# VOLTAGE_MONITOR.net
KiCad netlist of a schematic drawn in Altium Designer
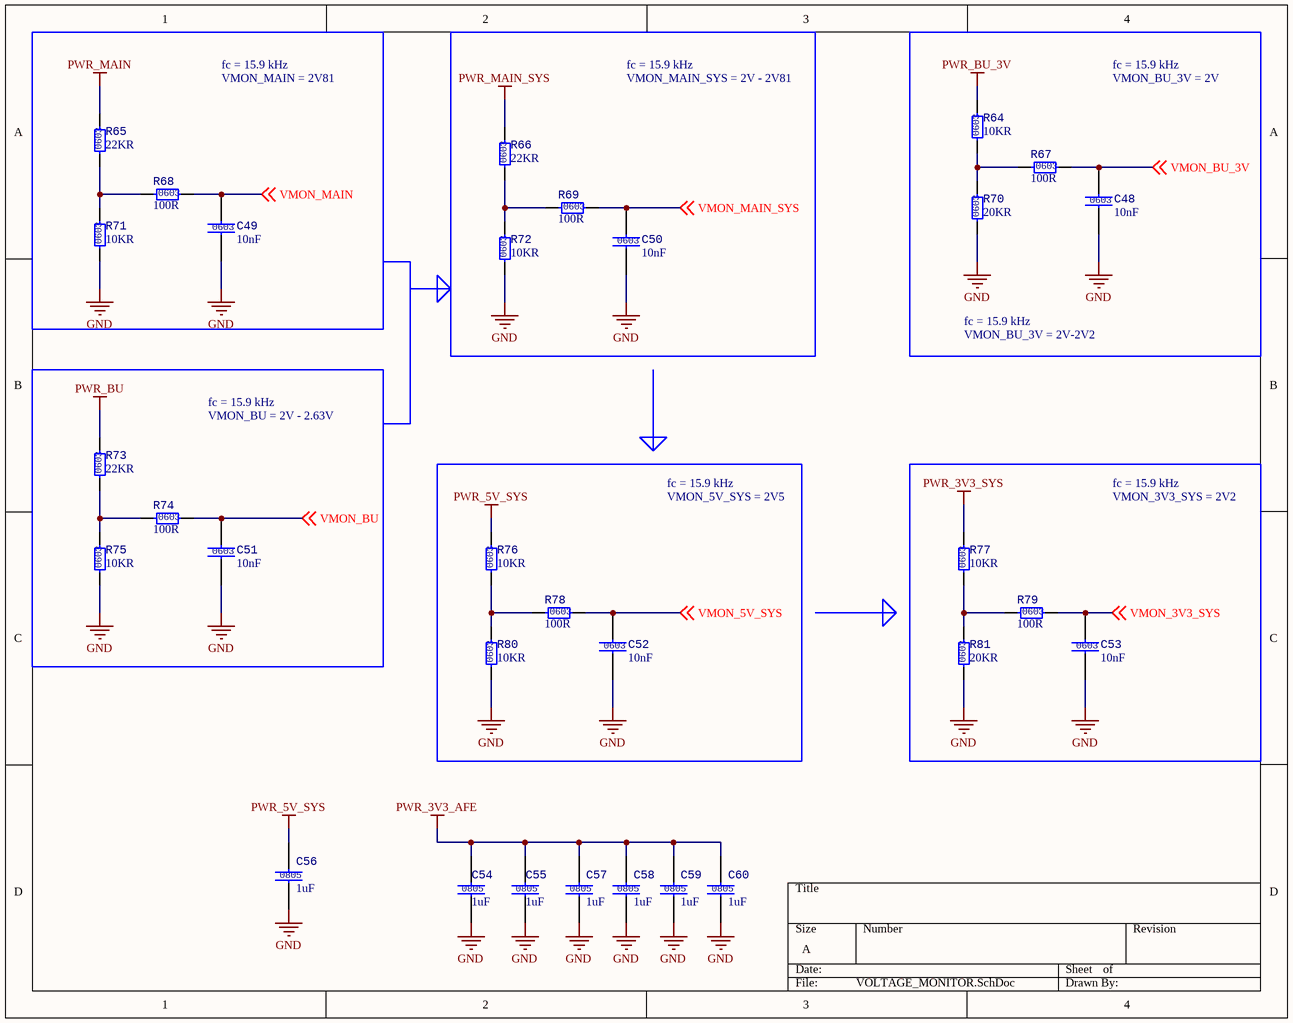
[diagram p0: VOLTAGE_MONITOR.SchDoc]

(export (version "E")
  (design (tool "Eeschema 10.0.6"))
  (components
    (comp (ref "C48")
      (value "10nF")
      (footprint "CAPCER 0805 SMD")
      (description "CAPACITOR SMD 0.01uF 50V 10% 0603")
      (fields
        (field (name "SIZE") "0603")
        (field (name "TOLERANCE") "10%")
        (field (name "Comment") "Tụ Gốm 0603 10nF 50V")
      )
      (libsource (lib "Database_Libs1") (part "CAPACITOR"))
    )
    (comp (ref "C49")
      (value "10nF")
      (footprint "CAPCER 0805 SMD")
      (description "CAPACITOR SMD 0.01uF 50V 10% 0603")
      (fields
        (field (name "SIZE") "0603")
        (field (name "TOLERANCE") "10%")
        (field (name "Comment") "Tụ Gốm 0603 10nF 50V")
      )
      (libsource (lib "Database_Libs1") (part "CAPACITOR"))
    )
    (comp (ref "C50")
      (value "10nF")
      (footprint "CAPCER 0805 SMD")
      (description "CAPACITOR SMD 0.01uF 50V 10% 0603")
      (fields
        (field (name "SIZE") "0603")
        (field (name "TOLERANCE") "10%")
        (field (name "Comment") "Tụ Gốm 0603 10nF 50V")
      )
      (libsource (lib "Database_Libs1") (part "CAPACITOR"))
    )
    (comp (ref "C51")
      (value "10nF")
      (footprint "CAPCER 0805 SMD")
      (description "CAPACITOR SMD 0.01uF 50V 10% 0603")
      (fields
        (field (name "SIZE") "0603")
        (field (name "TOLERANCE") "10%")
        (field (name "Comment") "Tụ Gốm 0603 10nF 50V")
      )
      (libsource (lib "Database_Libs1") (part "CAPACITOR"))
    )
    (comp (ref "C52")
      (value "10nF")
      (footprint "CAPCER 0805 SMD")
      (description "CAPACITOR SMD 0.01uF 50V 10% 0603")
      (fields
        (field (name "SIZE") "0603")
        (field (name "TOLERANCE") "10%")
        (field (name "Comment") "Tụ Gốm 0603 10nF 50V")
      )
      (libsource (lib "Database_Libs1") (part "CAPACITOR"))
    )
    (comp (ref "C53")
      (value "10nF")
      (footprint "CAPCER 0805 SMD")
      (description "CAPACITOR SMD 0.01uF 50V 10% 0603")
      (fields
        (field (name "SIZE") "0603")
        (field (name "TOLERANCE") "10%")
        (field (name "Comment") "Tụ Gốm 0603 10nF 50V")
      )
      (libsource (lib "Database_Libs1") (part "CAPACITOR"))
    )
    (comp (ref "C54")
      (value "1uF")
      (footprint "CAPCER 0805 SMD")
      (description "CAPACITOR SMD 1uF 16V 10% 0805")
      (fields (field (name "SIZE") "0805") (field (name "TOLERANCE") "10%"))
      (libsource (lib "Database_Libs1") (part "CAPACITOR"))
    )
    (comp (ref "C55")
      (value "1uF")
      (footprint "CAPCER 0805 SMD")
      (description "CAPACITOR SMD 1uF 16V 10% 0805")
      (fields (field (name "SIZE") "0805") (field (name "TOLERANCE") "10%"))
      (libsource (lib "Database_Libs1") (part "CAPACITOR"))
    )
    (comp (ref "C56")
      (value "1uF")
      (footprint "CAPCER 0805 SMD")
      (description "CAPACITOR SMD 1uF 16V 10% 0805")
      (fields (field (name "SIZE") "0805") (field (name "TOLERANCE") "10%"))
      (libsource (lib "Database_Libs1") (part "CAPACITOR"))
    )
    (comp (ref "C57")
      (value "1uF")
      (footprint "CAPCER 0805 SMD")
      (description "CAPACITOR SMD 1uF 16V 10% 0805")
      (fields (field (name "SIZE") "0805") (field (name "TOLERANCE") "10%"))
      (libsource (lib "Database_Libs1") (part "CAPACITOR"))
    )
    (comp (ref "C58")
      (value "1uF")
      (footprint "CAPCER 0603 SMD")
      (description "CAPACITOR SMD 1uF 16V 10% 0805")
      (fields (field (name "SIZE") "0805") (field (name "TOLERANCE") "10%") (field (name "Comment") "10uF"))
      (libsource (lib "Database_Libs1") (part "CAPACITOR"))
    )
    (comp (ref "C59")
      (value "1uF")
      (footprint "CAPCER 0805 SMD")
      (description "CAPACITOR SMD 1uF 16V 10% 0805")
      (fields (field (name "SIZE") "0805") (field (name "TOLERANCE") "10%"))
      (libsource (lib "Database_Libs1") (part "CAPACITOR"))
    )
    (comp (ref "C60")
      (value "1uF")
      (footprint "CAPCER 0603 SMD")
      (description "CAPACITOR SMD 1uF 16V 10% 0805")
      (fields (field (name "SIZE") "0805") (field (name "TOLERANCE") "10%") (field (name "Comment") "10uF"))
      (libsource (lib "Database_Libs1") (part "CAPACITOR"))
    )
    (comp (ref "R64")
      (value "10KR")
      (footprint "RESC 0603(1608) SMD")
      (description "RESISTOR SMD 10KR OHM 1% 100mW 0603")
      (fields (field (name "SIZE") "0603") (field (name "TOLERANCE") "1%"))
      (libsource (lib "Database_Libs1") (part "RESISTOR"))
    )
    (comp (ref "R65")
      (value "22KR")
      (footprint "RESC 0603(1608) SMD")
      (description "Điện Trở 22 KOhm 0603 1%")
      (fields (field (name "SIZE") "0603"))
      (libsource (lib "") (part "RESISTOR_1"))
    )
    (comp (ref "R66")
      (value "22KR")
      (footprint "RESC 0603(1608) SMD")
      (description "Điện Trở 22 KOhm 0603 1%")
      (fields (field (name "SIZE") "0603"))
      (libsource (lib "") (part "RESISTOR_1"))
    )
    (comp (ref "R67")
      (value "100R")
      (footprint "RESC 0603(1608) SMD")
      (description "Điện Trở 100 Ohm 0603 1%")
      (fields (field (name "SIZE") "0603"))
      (libsource (lib "Database_Libs2") (part "RESISTOR"))
    )
    (comp (ref "R68")
      (value "100R")
      (footprint "RESC 0603(1608) SMD")
      (description "Điện Trở 100 Ohm 0603 1%")
      (fields (field (name "SIZE") "0603"))
      (libsource (lib "Database_Libs2") (part "RESISTOR"))
    )
    (comp (ref "R69")
      (value "100R")
      (footprint "RESC 0603(1608) SMD")
      (description "Điện Trở 100 Ohm 0603 1%")
      (fields (field (name "SIZE") "0603"))
      (libsource (lib "Database_Libs2") (part "RESISTOR"))
    )
    (comp (ref "R70")
      (value "20KR")
      (footprint "RESC 0603(1608) SMD")
      (description "Điện Trở 20 KOhm 0603 1%")
      (fields (field (name "SIZE") "0603"))
      (libsource (lib "") (part "RESISTOR_1"))
    )
    (comp (ref "R71")
      (value "10KR")
      (footprint "RESC 0603(1608) SMD")
      (description "RESISTOR SMD 10KR OHM 1% 100mW 0603")
      (fields (field (name "SIZE") "0603") (field (name "TOLERANCE") "1%"))
      (libsource (lib "Database_Libs1") (part "RESISTOR"))
    )
    (comp (ref "R72")
      (value "10KR")
      (footprint "RESC 0603(1608) SMD")
      (description "RESISTOR SMD 10KR OHM 1% 100mW 0603")
      (fields (field (name "SIZE") "0603") (field (name "TOLERANCE") "1%"))
      (libsource (lib "Database_Libs1") (part "RESISTOR"))
    )
    (comp (ref "R73")
      (value "22KR")
      (footprint "RESC 0603(1608) SMD")
      (description "Điện Trở 22 KOhm 0603 1%")
      (fields (field (name "SIZE") "0603"))
      (libsource (lib "") (part "RESISTOR_1"))
    )
    (comp (ref "R74")
      (value "100R")
      (footprint "RESC 0603(1608) SMD")
      (description "Điện Trở 100 Ohm 0603 1%")
      (fields (field (name "SIZE") "0603"))
      (libsource (lib "Database_Libs2") (part "RESISTOR"))
    )
    (comp (ref "R75")
      (value "10KR")
      (footprint "RESC 0603(1608) SMD")
      (description "RESISTOR SMD 10KR OHM 1% 100mW 0603")
      (fields (field (name "SIZE") "0603") (field (name "TOLERANCE") "1%"))
      (libsource (lib "Database_Libs1") (part "RESISTOR"))
    )
    (comp (ref "R76")
      (value "10KR")
      (footprint "RESC 0603(1608) SMD")
      (description "RESISTOR SMD 10KR OHM 1% 100mW 0603")
      (fields (field (name "SIZE") "0603") (field (name "TOLERANCE") "1%"))
      (libsource (lib "Database_Libs1") (part "RESISTOR"))
    )
    (comp (ref "R77")
      (value "10KR")
      (footprint "RESC 0603(1608) SMD")
      (description "RESISTOR SMD 10KR OHM 1% 100mW 0603")
      (fields (field (name "SIZE") "0603") (field (name "TOLERANCE") "1%"))
      (libsource (lib "Database_Libs1") (part "RESISTOR"))
    )
    (comp (ref "R78")
      (value "100R")
      (footprint "RESC 0603(1608) SMD")
      (description "Điện Trở 100 Ohm 0603 1%")
      (fields (field (name "SIZE") "0603"))
      (libsource (lib "Database_Libs2") (part "RESISTOR"))
    )
    (comp (ref "R79")
      (value "100R")
      (footprint "RESC 0603(1608) SMD")
      (description "Điện Trở 100 Ohm 0603 1%")
      (fields (field (name "SIZE") "0603"))
      (libsource (lib "Database_Libs2") (part "RESISTOR"))
    )
    (comp (ref "R80")
      (value "10KR")
      (footprint "RESC 0603(1608) SMD")
      (description "RESISTOR SMD 10KR OHM 1% 100mW 0603")
      (fields (field (name "SIZE") "0603") (field (name "TOLERANCE") "1%"))
      (libsource (lib "Database_Libs1") (part "RESISTOR"))
    )
    (comp (ref "R81")
      (value "20KR")
      (footprint "RESC 0603(1608) SMD")
      (description "Điện Trở 20 KOhm 0603 1%")
      (fields (field (name "SIZE") "0603"))
      (libsource (lib "") (part "RESISTOR_1"))
    )
  )
  (nets
    (net (code "1") (name "GND") (class "Default")
      (node (ref "C48") (pin "2") (pinfunction "2_2") (pintype "passive"))
      (node (ref "C49") (pin "2") (pinfunction "2_2") (pintype "passive"))
      (node (ref "C50") (pin "2") (pinfunction "2_2") (pintype "passive"))
      (node (ref "C51") (pin "2") (pinfunction "2_2") (pintype "passive"))
      (node (ref "C52") (pin "2") (pinfunction "2_2") (pintype "passive"))
      (node (ref "C53") (pin "2") (pinfunction "2_2") (pintype "passive"))
      (node (ref "C54") (pin "2") (pinfunction "2_2") (pintype "passive"))
      (node (ref "C55") (pin "2") (pinfunction "2_2") (pintype "passive"))
      (node (ref "C56") (pin "2") (pinfunction "2_2") (pintype "passive"))
      (node (ref "C57") (pin "2") (pinfunction "2_2") (pintype "passive"))
      (node (ref "C58") (pin "2") (pinfunction "2_2") (pintype "passive"))
      (node (ref "C59") (pin "2") (pinfunction "2_2") (pintype "passive"))
      (node (ref "C60") (pin "2") (pinfunction "2_2") (pintype "passive"))
      (node (ref "R70") (pin "1") (pinfunction "1_1") (pintype "passive"))
      (node (ref "R71") (pin "1") (pinfunction "1_1") (pintype "passive"))
      (node (ref "R72") (pin "1") (pinfunction "1_1") (pintype "passive"))
      (node (ref "R75") (pin "1") (pinfunction "1_1") (pintype "passive"))
      (node (ref "R80") (pin "1") (pinfunction "1_1") (pintype "passive"))
      (node (ref "R81") (pin "1") (pinfunction "1_1") (pintype "passive"))
    )
    (net (code "2") (name "Net-(R64-Pad1)") (class "Default")
      (node (ref "R64") (pin "1") (pinfunction "1_1") (pintype "passive"))
      (node (ref "R67") (pin "1") (pinfunction "1_1") (pintype "passive"))
      (node (ref "R70") (pin "2") (pinfunction "2_2") (pintype "passive"))
    )
    (net (code "3") (name "Net-(R65-Pad1)") (class "Default")
      (node (ref "R65") (pin "1") (pinfunction "1_1") (pintype "passive"))
      (node (ref "R68") (pin "1") (pinfunction "1_1") (pintype "passive"))
      (node (ref "R71") (pin "2") (pinfunction "2_2") (pintype "passive"))
    )
    (net (code "4") (name "Net-(R66-Pad1)") (class "Default")
      (node (ref "R66") (pin "1") (pinfunction "1_1") (pintype "passive"))
      (node (ref "R69") (pin "1") (pinfunction "1_1") (pintype "passive"))
      (node (ref "R72") (pin "2") (pinfunction "2_2") (pintype "passive"))
    )
    (net (code "5") (name "Net-(R73-Pad1)") (class "Default")
      (node (ref "R73") (pin "1") (pinfunction "1_1") (pintype "passive"))
      (node (ref "R74") (pin "1") (pinfunction "1_1") (pintype "passive"))
      (node (ref "R75") (pin "2") (pinfunction "2_2") (pintype "passive"))
    )
    (net (code "6") (name "Net-(R76-Pad1)") (class "Default")
      (node (ref "R76") (pin "1") (pinfunction "1_1") (pintype "passive"))
      (node (ref "R78") (pin "1") (pinfunction "1_1") (pintype "passive"))
      (node (ref "R80") (pin "2") (pinfunction "2_2") (pintype "passive"))
    )
    (net (code "7") (name "Net-(R77-Pad1)") (class "Default")
      (node (ref "R77") (pin "1") (pinfunction "1_1") (pintype "passive"))
      (node (ref "R79") (pin "1") (pinfunction "1_1") (pintype "passive"))
      (node (ref "R81") (pin "2") (pinfunction "2_2") (pintype "passive"))
    )
    (net (code "8") (name "PWR_3V3_AFE") (class "Default")
      (node (ref "C54") (pin "1") (pinfunction "1_1") (pintype "passive"))
      (node (ref "C55") (pin "1") (pinfunction "1_1") (pintype "passive"))
      (node (ref "C57") (pin "1") (pinfunction "1_1") (pintype "passive"))
      (node (ref "C58") (pin "1") (pinfunction "1_1") (pintype "passive"))
      (node (ref "C59") (pin "1") (pinfunction "1_1") (pintype "passive"))
      (node (ref "C60") (pin "1") (pinfunction "1_1") (pintype "passive"))
    )
    (net (code "9") (name "PWR_3V3_SYS") (class "Default")
      (node (ref "R77") (pin "2") (pinfunction "2_2") (pintype "passive"))
    )
    (net (code "10") (name "PWR_5V_SYS") (class "Default")
      (node (ref "C56") (pin "1") (pinfunction "1_1") (pintype "passive"))
      (node (ref "R76") (pin "2") (pinfunction "2_2") (pintype "passive"))
    )
    (net (code "11") (name "PWR_BU") (class "Default")
      (node (ref "R73") (pin "2") (pinfunction "2_2") (pintype "passive"))
    )
    (net (code "12") (name "PWR_BU_3V") (class "Default")
      (node (ref "R64") (pin "2") (pinfunction "2_2") (pintype "passive"))
    )
    (net (code "13") (name "PWR_MAIN") (class "Default")
      (node (ref "R65") (pin "2") (pinfunction "2_2") (pintype "passive"))
    )
    (net (code "14") (name "PWR_MAIN_SYS") (class "Default")
      (node (ref "R66") (pin "2") (pinfunction "2_2") (pintype "passive"))
    )
    (net (code "15") (name "VMON_3V3_SYS") (class "Default")
      (node (ref "C53") (pin "1") (pinfunction "1_1") (pintype "passive"))
      (node (ref "R79") (pin "2") (pinfunction "2_2") (pintype "passive"))
    )
    (net (code "16") (name "VMON_5V_SYS") (class "Default")
      (node (ref "C52") (pin "1") (pinfunction "1_1") (pintype "passive"))
      (node (ref "R78") (pin "2") (pinfunction "2_2") (pintype "passive"))
    )
    (net (code "17") (name "VMON_BU") (class "Default")
      (node (ref "C51") (pin "1") (pinfunction "1_1") (pintype "passive"))
      (node (ref "R74") (pin "2") (pinfunction "2_2") (pintype "passive"))
    )
    (net (code "18") (name "VMON_BU_3V") (class "Default")
      (node (ref "C48") (pin "1") (pinfunction "1_1") (pintype "passive"))
      (node (ref "R67") (pin "2") (pinfunction "2_2") (pintype "passive"))
    )
    (net (code "19") (name "VMON_MAIN") (class "Default")
      (node (ref "C49") (pin "1") (pinfunction "1_1") (pintype "passive"))
      (node (ref "R68") (pin "2") (pinfunction "2_2") (pintype "passive"))
    )
    (net (code "20") (name "VMON_MAIN_SYS") (class "Default")
      (node (ref "C50") (pin "1") (pinfunction "1_1") (pintype "passive"))
      (node (ref "R69") (pin "2") (pinfunction "2_2") (pintype "passive"))
    )
  )
)
